# pca10112_sheet8_FEM.net
KiCad netlist of a schematic drawn in Altium Designer
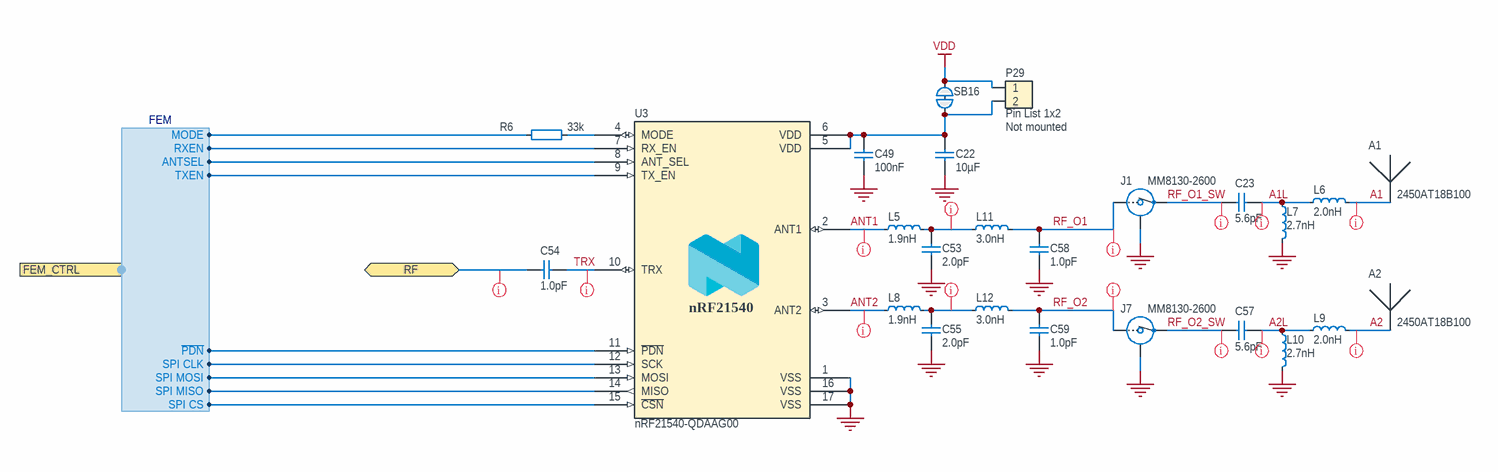
[diagram p0: pca10112_sheet8_FEM.SchDoc]

(export (version "E")
  (design (tool "Eeschema 10.0.6"))
  (components
    (comp (ref "A1")
      (value "2450AT18B100")
      (footprint "2450AT18B100")
      (description "2.45 GHz chip antenna")
      (fields
        (field (name "PART NUMBER") "Johanson 2450AT18B100")
        (field (name "MANUFACTURER") "Johanson Technology")
        (field (name "AUTHOR") "rsk")
      )
      (libsource (lib "AltiumLib") (part "Antenna"))
    )
    (comp (ref "A2")
      (value "2450AT18B100")
      (footprint "2450AT18B100")
      (description "2.45 GHz chip antenna")
      (fields
        (field (name "PART NUMBER") "Johanson 2450AT18B100")
        (field (name "MANUFACTURER") "Johanson Technology")
        (field (name "AUTHOR") "rsk")
      )
      (libsource (lib "AltiumLib") (part "Antenna"))
    )
    (comp (ref "C22")
      (value "10µF")
      (footprint "CAPC1608X06L")
      (description "Capacitor, X5R, ±20%")
      (fields
        (field (name "PART NUMBER") "C0603-10µ")
        (field (name "MANUFACTURER") "N.A.")
        (field (name "AUTHOR") "rsk")
      )
      (libsource (lib "AltiumLib") (part "CAP"))
    )
    (comp (ref "C23")
      (value "5.6pF")
      (footprint "CAPC0603X03L_C")
      (description "Capacitor, C0G, ±0.05pF, 50V")
      (fields
        (field (name "PART NUMBER") "C0201-5.6p")
        (field (name "MANUFACTURER") "N.A.")
        (field (name "AUTHOR") "rsk")
      )
      (libsource (lib "AltiumLib") (part "CAP"))
    )
    (comp (ref "C49")
      (value "100nF")
      (footprint "CAPC0603X03L_C")
      (description "Capacitor, X5R, ±10%")
      (fields
        (field (name "PART NUMBER") "C0201-100n")
        (field (name "MANUFACTURER") "N.A.")
        (field (name "AUTHOR") "rsk")
      )
      (libsource (lib "AltiumLib") (part "CAP"))
    )
    (comp (ref "C53")
      (value "2.0pF")
      (footprint "CAPC0603X03L_C")
      (description "Capacitor, NP0, ±0.05pF, 25V")
      (fields
        (field (name "PART NUMBER") "C0201-2.0p-HQ-Murata")
        (field (name "MANUFACTURER") "Murata")
        (field (name "AUTHOR") "rsk")
      )
      (libsource (lib "AltiumLib") (part "CAP"))
    )
    (comp (ref "C54")
      (value "1.0pF")
      (footprint "CAPC0603X03L_C")
      (description "Capacitor, C0G, ±0.1pF, 25V")
      (fields
        (field (name "PART NUMBER") "C0201-1p0")
        (field (name "MANUFACTURER") "Murata")
        (field (name "AUTHOR") "rsk")
      )
      (libsource (lib "AltiumLib") (part "CAP"))
    )
    (comp (ref "C55")
      (value "2.0pF")
      (footprint "CAPC0603X03L_C")
      (description "Capacitor, NP0, ±0.05pF, 25V")
      (fields
        (field (name "PART NUMBER") "C0201-2.0p-HQ-Murata")
        (field (name "MANUFACTURER") "Murata")
        (field (name "AUTHOR") "rsk")
      )
      (libsource (lib "AltiumLib") (part "CAP"))
    )
    (comp (ref "C57")
      (value "5.6pF")
      (footprint "CAPC0603X03L_C")
      (description "Capacitor, C0G, ±0.05pF, 50V")
      (fields
        (field (name "PART NUMBER") "C0201-5.6p")
        (field (name "MANUFACTURER") "N.A.")
        (field (name "AUTHOR") "rsk")
      )
      (libsource (lib "AltiumLib") (part "CAP"))
    )
    (comp (ref "C58")
      (value "1.0pF")
      (footprint "CAPC0603X03L_C")
      (description "RF Chip Cap 0201")
      (fields
        (field (name "PART NUMBER") "C0201-1.0p_RF")
        (field (name "MANUFACTURER") "N.A.")
        (field (name "AUTHOR") "rsk")
      )
      (libsource (lib "AltiumLib") (part "CAP"))
    )
    (comp (ref "C59")
      (value "1.0pF")
      (footprint "CAPC0603X03L_C")
      (description "RF Chip Cap 0201")
      (fields
        (field (name "PART NUMBER") "C0201-1.0p_RF")
        (field (name "MANUFACTURER") "N.A.")
        (field (name "AUTHOR") "rsk")
      )
      (libsource (lib "AltiumLib") (part "CAP"))
    )
    (comp (ref "J1")
      (value "MM8130-2600")
      (footprint "COAXIAL-SWF")
      (description "Coaxial Connector with Switch")
      (fields (field (name "MANUFACTURER") "Murata") (field (name "AUTHOR") "rsk"))
      (libsource (lib "AltiumLib") (part "Coaxial-Internal-SW"))
    )
    (comp (ref "J7")
      (value "MM8130-2600")
      (footprint "COAXIAL-SWF")
      (description "Coaxial Connector with Switch")
      (fields (field (name "MANUFACTURER") "Murata") (field (name "AUTHOR") "rsk"))
      (libsource (lib "AltiumLib") (part "Coaxial-Internal-SW"))
    )
    (comp (ref "L5")
      (value "1.9nH")
      (footprint "INDC0603X03L_C")
      (description "Inductor, 600mA, ±0.1ｎH, 120mOhm")
      (fields
        (field (name "PART NUMBER") "L0201-1n9-HQ-Murata")
        (field (name "MANUFACTURER") "Murata")
        (field (name "AUTHOR") "rsk")
      )
      (libsource (lib "AltiumLib") (part "IND"))
    )
    (comp (ref "L6")
      (value "2.0nH")
      (footprint "INDC0603X03L_C")
      (description "Inductor, 600mA, ±0.1ｎH, 120mOhm")
      (fields
        (field (name "PART NUMBER") "L0201-2n0-HQ-Murata")
        (field (name "MANUFACTURER") "Murata")
        (field (name "AUTHOR") "rsk")
      )
      (libsource (lib "AltiumLib") (part "IND"))
    )
    (comp (ref "L7")
      (value "2.7nH")
      (footprint "INDC0603X03L_C")
      (description "Inductor, 600mA, ±0.1ｎH, 120mOhm")
      (fields
        (field (name "PART NUMBER") "L0201-2n7-HQ-Murata")
        (field (name "MANUFACTURER") "Murata")
        (field (name "AUTHOR") "rsk")
      )
      (libsource (lib "AltiumLib") (part "IND"))
    )
    (comp (ref "L8")
      (value "1.9nH")
      (footprint "INDC0603X03L_C")
      (description "Inductor, 600mA, ±0.1ｎH, 120mOhm")
      (fields
        (field (name "PART NUMBER") "L0201-1n9-HQ-Murata")
        (field (name "MANUFACTURER") "Murata")
        (field (name "AUTHOR") "rsk")
      )
      (libsource (lib "AltiumLib") (part "IND"))
    )
    (comp (ref "L9")
      (value "2.0nH")
      (footprint "INDC0603X03L_C")
      (description "Inductor, 600mA, ±0.1ｎH, 120mOhm")
      (fields
        (field (name "PART NUMBER") "L0201-2n0-HQ-Murata")
        (field (name "MANUFACTURER") "Murata")
        (field (name "AUTHOR") "rsk")
      )
      (libsource (lib "AltiumLib") (part "IND"))
    )
    (comp (ref "L10")
      (value "2.7nH")
      (footprint "INDC0603X03L_C")
      (description "Inductor, 600mA, ±0.1ｎH, 120mOhm")
      (fields
        (field (name "PART NUMBER") "L0201-2n7-HQ-Murata")
        (field (name "MANUFACTURER") "Murata")
        (field (name "AUTHOR") "rsk")
      )
      (libsource (lib "AltiumLib") (part "IND"))
    )
    (comp (ref "L11")
      (value "3.0nH")
      (footprint "INDC0603X03L_C")
      (description "Inductor, 600mA, ±0.1ｎH, 120mOhm")
      (fields
        (field (name "PART NUMBER") "L0201-3n0-HQ-Murata")
        (field (name "MANUFACTURER") "Murata")
        (field (name "AUTHOR") "rsk")
      )
      (libsource (lib "AltiumLib") (part "IND"))
    )
    (comp (ref "L12")
      (value "3.0nH")
      (footprint "INDC0603X03L_C")
      (description "Inductor, 600mA, ±0.1ｎH, 120mOhm")
      (fields
        (field (name "PART NUMBER") "L0201-3n0-HQ-Murata")
        (field (name "MANUFACTURER") "Murata")
        (field (name "AUTHOR") "rsk")
      )
      (libsource (lib "AltiumLib") (part "IND"))
    )
    (comp (ref "P29")
      (value "Pin List 1x2")
      (footprint "LIST_1x2-NC")
      (description "Pin List 1x2, 2.54mm (100mil)")
      (fields
        (field (name "PART NUMBER") "Pin List 1x2, N.C.")
        (field (name "ASSEMBLY") "Not mounted")
        (field (name "MANUFACTURER") "N.A.")
        (field (name "AUTHOR") "rsk")
      )
      (libsource (lib "AltiumLib") (part "CONN-2"))
    )
    (comp (ref "R6")
      (value "33k")
      (footprint "RESC0603X03L_C")
      (description "Resistor, ±1%, 0.05W")
      (fields
        (field (name "PART NUMBER") "R0201-33k")
        (field (name "MANUFACTURER") "N.A.")
        (field (name "AUTHOR") "rsk")
      )
      (libsource (lib "AltiumLib") (part "RES"))
    )
    (comp (ref "SB16")
      (value "Solderbridge")
      (footprint "Solderbridge_Shorted")
      (description "Shorted Solderbridge")
      (fields
        (field (name "PART NUMBER") "Solderbridge Shorted")
        (field (name "MANUFACTURER") "N.A.")
        (field (name "AUTHOR") "rsk")
      )
      (libsource (lib "AltiumLib") (part "SOLDERBRIDGE_SHORTED"))
    )
    (comp (ref "U3")
      (value "nRF21540-QDAAG00")
      (footprint "QFN65P400X400X65_HS-17N")
      (description "Radio front-end / range extender for 2.4GHz")
      (fields
        (field (name "MANUFACTURER") "Nordic Semiconductor")
        (field (name "PART NUMBER") "nRF21540-QDAAG0")
        (field (name "AUTHOR") "hany")
      )
      (libsource (lib "AltiumLib") (part "nRF21540-QDAA"))
    )
  )
  (nets
    (net (code "2") (name "/A1") (class "Default")
      (node (ref "A1") (pin "1") (pinfunction "1_1") (pintype "passive"))
      (node (ref "L6") (pin "2") (pinfunction "2_2") (pintype "passive"))
    )
    (net (code "3") (name "/A1L") (class "Default")
      (node (ref "C23") (pin "1") (pinfunction "1_1") (pintype "passive"))
      (node (ref "L6") (pin "1") (pinfunction "1_1") (pintype "passive"))
      (node (ref "L7") (pin "1") (pinfunction "1_1") (pintype "passive"))
    )
    (net (code "4") (name "/A2") (class "Default")
      (node (ref "A2") (pin "1") (pinfunction "1_1") (pintype "passive"))
      (node (ref "L9") (pin "2") (pinfunction "2_2") (pintype "passive"))
    )
    (net (code "5") (name "/A2L") (class "Default")
      (node (ref "C57") (pin "1") (pinfunction "1_1") (pintype "passive"))
      (node (ref "L10") (pin "1") (pinfunction "1_1") (pintype "passive"))
      (node (ref "L9") (pin "1") (pinfunction "1_1") (pintype "passive"))
    )
    (net (code "6") (name "/ANT1") (class "Default")
      (node (ref "L5") (pin "1") (pinfunction "1_1") (pintype "passive"))
      (node (ref "U3") (pin "2") (pinfunction "ANT1_2") (pintype "bidirectional"))
    )
    (net (code "7") (name "/ANT2") (class "Default")
      (node (ref "L8") (pin "1") (pinfunction "1_1") (pintype "passive"))
      (node (ref "U3") (pin "3") (pinfunction "ANT2_3") (pintype "bidirectional"))
    )
    (net (code "8") (name "/ANTSEL") (class "Default")
      (node (ref "U3") (pin "8") (pinfunction "ANT_SEL_8") (pintype "input"))
    )
    (net (code "9") (name "/MODE") (class "Default")
      (node (ref "R6") (pin "1") (pinfunction "1_1") (pintype "passive"))
    )
    (net (code "10") (name "/RF") (class "Default")
      (node (ref "C54") (pin "1") (pinfunction "1_1") (pintype "passive"))
    )
    (net (code "11") (name "/RF_O1") (class "Default")
      (node (ref "C58") (pin "2") (pinfunction "2_2") (pintype "passive"))
      (node (ref "J1") (pin "1") (pinfunction "IN_1") (pintype "passive"))
      (node (ref "L11") (pin "2") (pinfunction "2_2") (pintype "passive"))
    )
    (net (code "12") (name "/RF_O1_SW") (class "Default")
      (node (ref "C23") (pin "2") (pinfunction "2_2") (pintype "passive"))
      (node (ref "J1") (pin "3") (pinfunction "OUT_3") (pintype "passive"))
    )
    (net (code "13") (name "/RF_O2") (class "Default")
      (node (ref "C59") (pin "2") (pinfunction "2_2") (pintype "passive"))
      (node (ref "J7") (pin "1") (pinfunction "IN_1") (pintype "passive"))
      (node (ref "L12") (pin "2") (pinfunction "2_2") (pintype "passive"))
    )
    (net (code "14") (name "/RF_O2_SW") (class "Default")
      (node (ref "C57") (pin "2") (pinfunction "2_2") (pintype "passive"))
      (node (ref "J7") (pin "3") (pinfunction "OUT_3") (pintype "passive"))
    )
    (net (code "15") (name "/RXEN") (class "Default")
      (node (ref "U3") (pin "7") (pinfunction "RX_EN_7") (pintype "input"))
    )
    (net (code "16") (name "/SPI CLK") (class "Default")
      (node (ref "U3") (pin "12") (pinfunction "SCK_12") (pintype "input"))
    )
    (net (code "17") (name "/SPI CS") (class "Default")
      (node (ref "U3") (pin "15") (pinfunction "~{CSN}_15") (pintype "input"))
    )
    (net (code "18") (name "/SPI MISO") (class "Default")
      (node (ref "U3") (pin "14") (pinfunction "MISO_14") (pintype "output"))
    )
    (net (code "19") (name "/SPI MOSI") (class "Default")
      (node (ref "U3") (pin "13") (pinfunction "MOSI_13") (pintype "input"))
    )
    (net (code "20") (name "/TRX") (class "Default")
      (node (ref "C54") (pin "2") (pinfunction "2_2") (pintype "passive"))
      (node (ref "U3") (pin "10") (pinfunction "TRX_10") (pintype "bidirectional"))
    )
    (net (code "21") (name "/TXEN") (class "Default")
      (node (ref "U3") (pin "9") (pinfunction "TX_EN_9") (pintype "input"))
    )
    (net (code "23") (name "/~{PDN}") (class "Default")
      (node (ref "U3") (pin "11") (pinfunction "~{PDN}_11") (pintype "input"))
    )
    (net (code "24") (name "GND") (class "Default")
      (node (ref "C22") (pin "1") (pinfunction "1_1") (pintype "passive"))
      (node (ref "C49") (pin "1") (pinfunction "1_1") (pintype "passive"))
      (node (ref "C53") (pin "1") (pinfunction "1_1") (pintype "passive"))
      (node (ref "C55") (pin "1") (pinfunction "1_1") (pintype "passive"))
      (node (ref "C58") (pin "1") (pinfunction "1_1") (pintype "passive"))
      (node (ref "C59") (pin "1") (pinfunction "1_1") (pintype "passive"))
      (node (ref "J1") (pin "2") (pinfunction "Shield_2") (pintype "passive"))
      (node (ref "J7") (pin "2") (pinfunction "Shield_2") (pintype "passive"))
      (node (ref "L10") (pin "2") (pinfunction "2_2") (pintype "passive"))
      (node (ref "L7") (pin "2") (pinfunction "2_2") (pintype "passive"))
      (node (ref "U3") (pin "1") (pinfunction "VSS_1") (pintype "power_in"))
      (node (ref "U3") (pin "16") (pinfunction "VSS_16") (pintype "power_in"))
      (node (ref "U3") (pin "17") (pinfunction "VSS_17") (pintype "power_in"))
    )
    (net (code "25") (name "Net-(C53-Pad2)") (class "Default")
      (node (ref "C53") (pin "2") (pinfunction "2_2") (pintype "passive"))
      (node (ref "L11") (pin "1") (pinfunction "1_1") (pintype "passive"))
      (node (ref "L5") (pin "2") (pinfunction "2_2") (pintype "passive"))
    )
    (net (code "26") (name "Net-(C55-Pad2)") (class "Default")
      (node (ref "C55") (pin "2") (pinfunction "2_2") (pintype "passive"))
      (node (ref "L12") (pin "1") (pinfunction "1_1") (pintype "passive"))
      (node (ref "L8") (pin "2") (pinfunction "2_2") (pintype "passive"))
    )
    (net (code "27") (name "Net-(SB16-1)") (class "Default")
      (node (ref "C22") (pin "2") (pinfunction "2_2") (pintype "passive"))
      (node (ref "C49") (pin "2") (pinfunction "2_2") (pintype "passive"))
      (node (ref "P29") (pin "2") (pinfunction "2_2") (pintype "passive"))
      (node (ref "SB16") (pin "2") (pinfunction "1_2") (pintype "passive"))
      (node (ref "U3") (pin "5") (pinfunction "VDD_5") (pintype "power_in"))
      (node (ref "U3") (pin "6") (pinfunction "VDD_6") (pintype "power_in"))
    )
    (net (code "28") (name "Net-(U3-MODE)") (class "Default")
      (node (ref "R6") (pin "2") (pinfunction "2_2") (pintype "passive"))
      (node (ref "U3") (pin "4") (pinfunction "MODE_4") (pintype "bidirectional"))
    )
    (net (code "29") (name "VDD") (class "Default")
      (node (ref "P29") (pin "1") (pinfunction "1_1") (pintype "passive"))
      (node (ref "SB16") (pin "1") (pinfunction "0_1") (pintype "passive"))
    )
  )
)
